# Domino_Pi.net
KiCad netlist of a schematic drawn in EAGLE
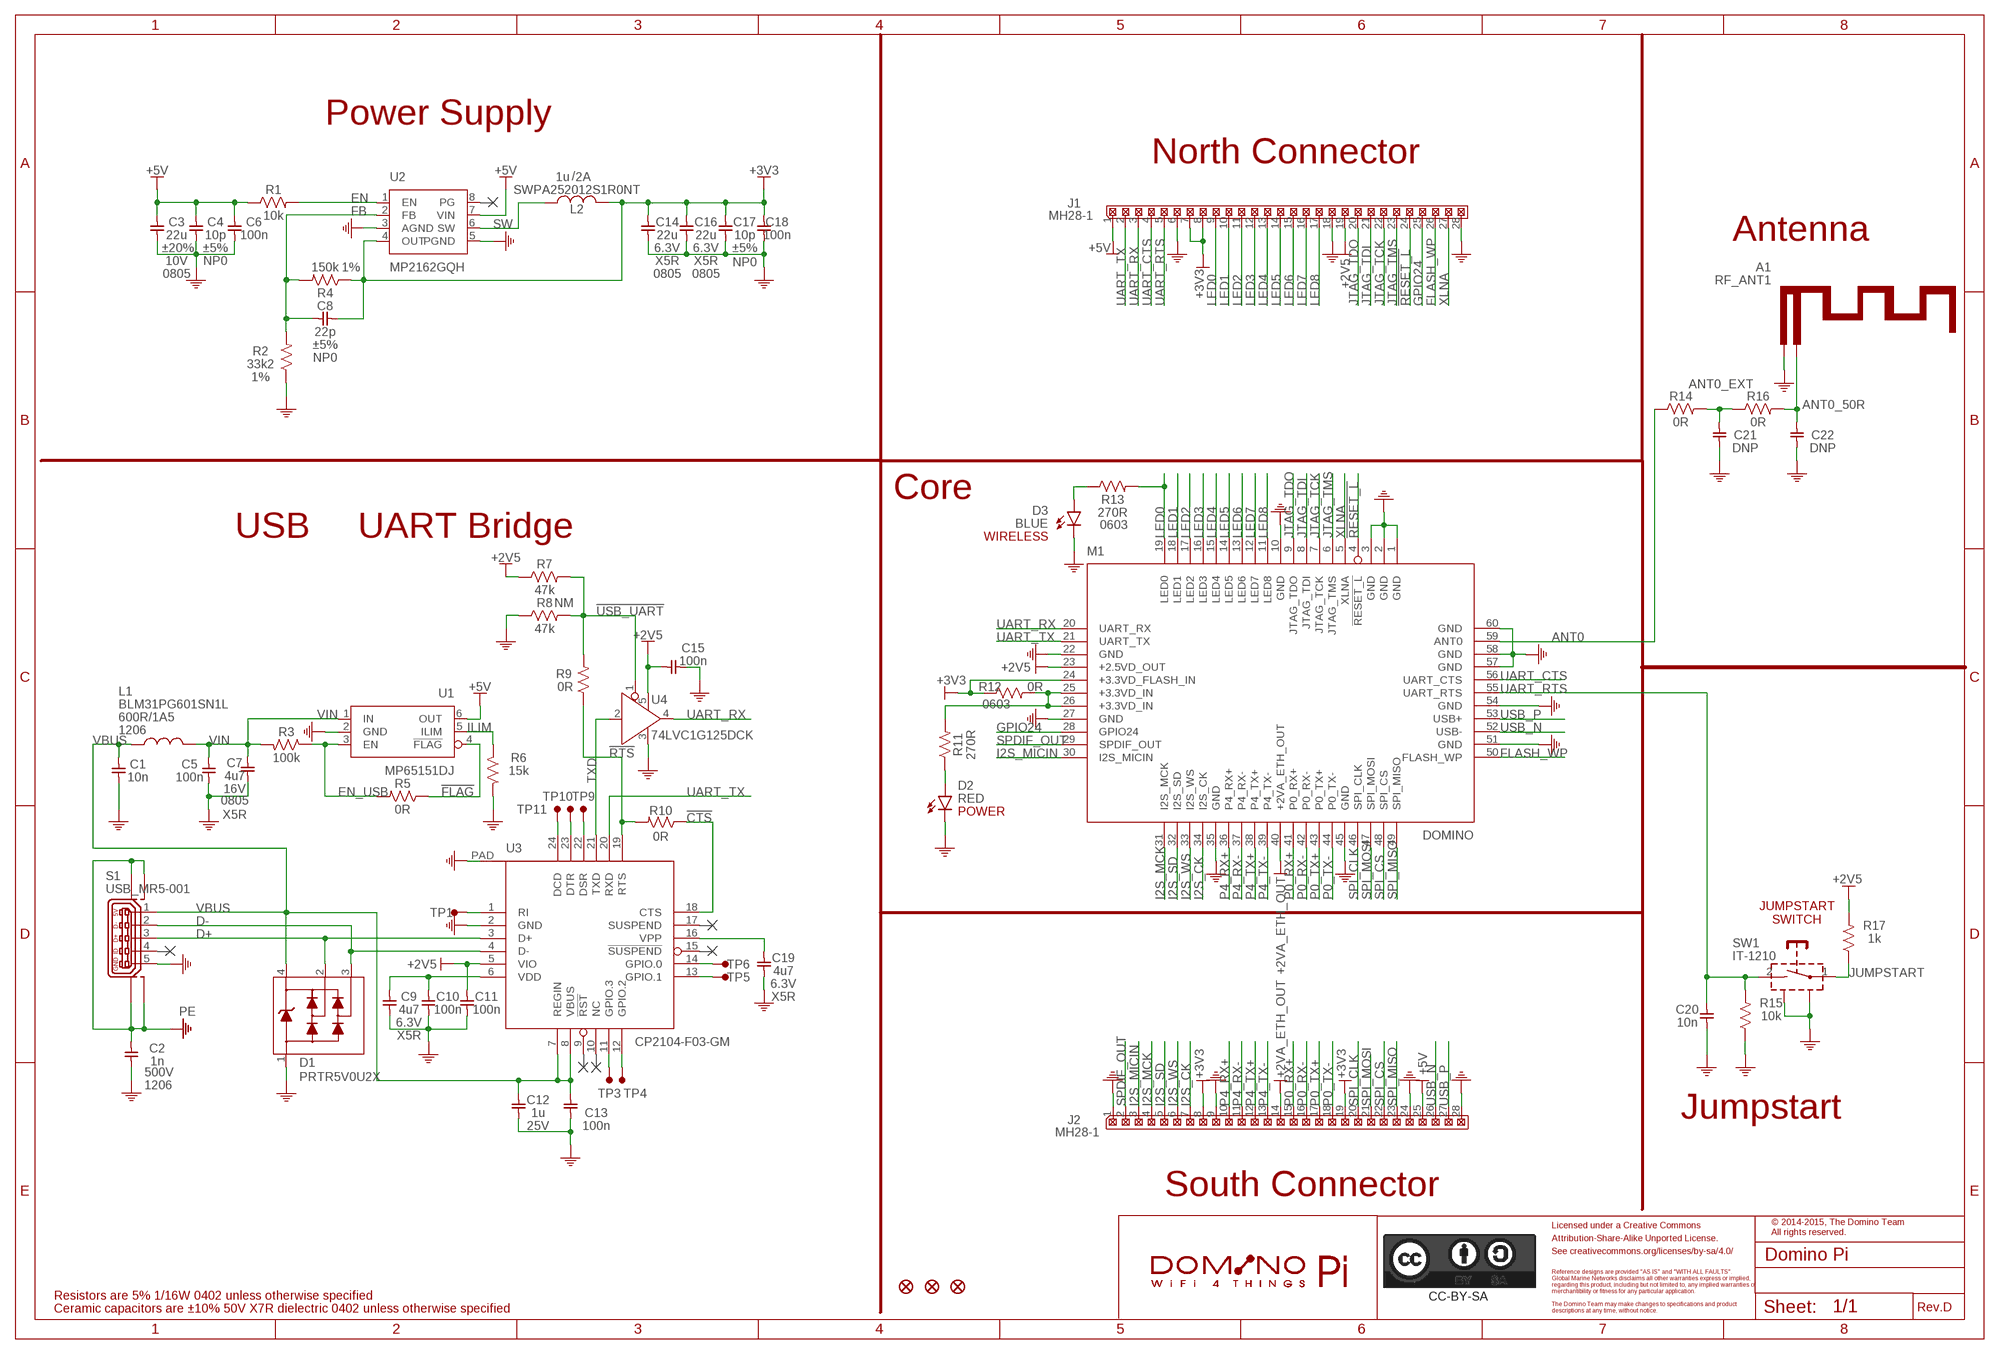
[diagram p0: schematic, sheet 1]

(export (version "E")
  (design (tool "Eeschema 10.0.6"))
  (components
    (comp (ref "A1")
      (value "RF_ANT1")
      (footprint "eagle-import:RF_ANT1")
      (fields (field (name "PARTNO") "WIFI_ANT-2.4GHz"))
      (libsource (lib "eagle-import") (part "RF_ANT1"))
    )
    (comp (ref "C1")
      (value "10n")
      (footprint "eagle-import:C0402")
      (fields (field (name "PARTNO") "C0402_10n_X7R_10%_CER_50V"))
      (libsource (lib "eagle-import") (part "CAP_0402"))
    )
    (comp (ref "C2")
      (value "1n")
      (footprint "eagle-import:C1206")
      (fields
        (field (name "SIZE") "1206")
        (field (name "PARTNO") "C1206_1n_X7R_10%_CER_500V")
        (field (name "VOLT") "500V")
      )
      (libsource (lib "eagle-import") (part "CAP_1206"))
    )
    (comp (ref "C3")
      (value "22u")
      (footprint "eagle-import:C0805")
      (fields
        (field (name "SIZE") "0805")
        (field (name "PARTNO") "C1206_22u_X7R_20%_CER_10V")
        (field (name "TOL") "±20%")
        (field (name "VOLT") "10V")
      )
      (libsource (lib "eagle-import") (part "CAP_0805"))
    )
    (comp (ref "C4")
      (value "10p")
      (footprint "eagle-import:C0402")
      (fields
        (field (name "PARTNO") "C0402_10p_NP0_5%_CER_50V")
        (field (name "TC") "NP0")
        (field (name "TOL") "±5%")
      )
      (libsource (lib "eagle-import") (part "CAP_0402"))
    )
    (comp (ref "C5")
      (value "100n")
      (footprint "eagle-import:C0402")
      (fields (field (name "PARTNO") "C0402_100n_X7R_10%_CER_50V"))
      (libsource (lib "eagle-import") (part "CAP_0402"))
    )
    (comp (ref "C6")
      (value "100n")
      (footprint "eagle-import:C0402")
      (fields (field (name "PARTNO") "C0402_100n_X7R_10%_CER_50V"))
      (libsource (lib "eagle-import") (part "CAP_0402"))
    )
    (comp (ref "C7")
      (value "4u7")
      (footprint "eagle-import:C0805")
      (fields
        (field (name "SIZE") "0805")
        (field (name "PARTNO") "C0805_4u7_X5R_10%_CER_16V")
        (field (name "TC") "X5R")
        (field (name "VOLT") "16V")
      )
      (libsource (lib "eagle-import") (part "CAP_0805"))
    )
    (comp (ref "C8")
      (value "22p")
      (footprint "eagle-import:C0402")
      (fields
        (field (name "PARTNO") "C0402_22p_NP0_5%_CER_50V")
        (field (name "TC") "NP0")
        (field (name "TOL") "±5%")
      )
      (libsource (lib "eagle-import") (part "CAP_0402"))
    )
    (comp (ref "C9")
      (value "4u7")
      (footprint "eagle-import:C0402")
      (fields
        (field (name "PARTNO") "C0402_4u7_X5R_10%_CER_6V3")
        (field (name "TC") "X5R")
        (field (name "VOLT") "6.3V")
      )
      (libsource (lib "eagle-import") (part "CAP_0402"))
    )
    (comp (ref "C10")
      (value "100n")
      (footprint "eagle-import:C0402")
      (fields (field (name "PARTNO") "C0402_100n_X7R_10%_CER_50V"))
      (libsource (lib "eagle-import") (part "CAP_0402"))
    )
    (comp (ref "C11")
      (value "100n")
      (footprint "eagle-import:C0402")
      (fields (field (name "PARTNO") "C0402_100n_X7R_10%_CER_50V"))
      (libsource (lib "eagle-import") (part "CAP_0402"))
    )
    (comp (ref "C12")
      (value "1u")
      (footprint "eagle-import:C0402")
      (fields (field (name "PARTNO") "C0402_1u_X7R_10%_CER_25V") (field (name "VOLT") "25V"))
      (libsource (lib "eagle-import") (part "CAP_0402"))
    )
    (comp (ref "C13")
      (value "100n")
      (footprint "eagle-import:C0402")
      (fields (field (name "PARTNO") "C0402_100n_X7R_10%_CER_50V"))
      (libsource (lib "eagle-import") (part "CAP_0402"))
    )
    (comp (ref "C14")
      (value "22u")
      (footprint "eagle-import:C0805")
      (fields
        (field (name "SIZE") "0805")
        (field (name "PARTNO") "C0805_22u_X5R_20%_CER_6V3")
        (field (name "TC") "X5R")
        (field (name "VOLT") "6.3V")
      )
      (libsource (lib "eagle-import") (part "CAP_0805"))
    )
    (comp (ref "C15")
      (value "100n")
      (footprint "eagle-import:C0402")
      (fields (field (name "PARTNO") "C0402_100n_X7R_10%_CER_50V"))
      (libsource (lib "eagle-import") (part "CAP_0402"))
    )
    (comp (ref "C16")
      (value "22u")
      (footprint "eagle-import:C0805")
      (fields
        (field (name "SIZE") "0805")
        (field (name "PARTNO") "C0805_22u_X5R_20%_CER_6V3")
        (field (name "TC") "X5R")
        (field (name "VOLT") "6.3V")
      )
      (libsource (lib "eagle-import") (part "CAP_0805"))
    )
    (comp (ref "C17")
      (value "10p")
      (footprint "eagle-import:C0402")
      (fields
        (field (name "PARTNO") "C0402_10p_NP0_5%_CER_50V")
        (field (name "TC") "NP0")
        (field (name "TOL") "±5%")
      )
      (libsource (lib "eagle-import") (part "CAP_0402"))
    )
    (comp (ref "C18")
      (value "100n")
      (footprint "eagle-import:C0402")
      (fields (field (name "PARTNO") "C0402_100n_X7R_10%_CER_50V"))
      (libsource (lib "eagle-import") (part "CAP_0402"))
    )
    (comp (ref "C19")
      (value "4u7")
      (footprint "eagle-import:C0402")
      (fields
        (field (name "PARTNO") "C0402_4u7_X5R_10%_CER_6V3")
        (field (name "TC") "X5R")
        (field (name "VOLT") "6.3V")
      )
      (libsource (lib "eagle-import") (part "CAP_0402"))
    )
    (comp (ref "C20")
      (value "10n")
      (footprint "eagle-import:C0402")
      (fields (field (name "PARTNO") "C0402_10n_X7R_10%_CER_50V"))
      (libsource (lib "eagle-import") (part "CAP_0402"))
    )
    (comp (ref "C21")
      (value "DNP")
      (footprint "eagle-import:C0402")
      (fields (field (name "PARTNO") "C0402_DNP"))
      (libsource (lib "eagle-import") (part "CAP_0402"))
    )
    (comp (ref "C22")
      (value "DNP")
      (footprint "eagle-import:C0402")
      (fields (field (name "PARTNO") "C0402_DNP"))
      (libsource (lib "eagle-import") (part "CAP_0402"))
    )
    (comp (ref "CC-BY-SA")
      (value "CC-BY-SA_LOGO")
      (footprint "eagle-import:CC-BY-SA_LOGO")
      (libsource (lib "eagle-import") (part "CC-BY-SA_LOGO"))
    )
    (comp (ref "D1")
      (value "PRTR5V0U2X")
      (footprint "eagle-import:SOT143B")
      (libsource (lib "eagle-import") (part "PRTR5V0U2X"))
    )
    (comp (ref "D2")
      (value "RED")
      (footprint "eagle-import:LED0402")
      (fields (field (name "PARTNO") "LED0402-RED"))
      (libsource (lib "eagle-import") (part "LED_0402"))
    )
    (comp (ref "D3")
      (value "BLUE")
      (footprint "eagle-import:LED0402")
      (fields (field (name "PARTNO") "LED0402-BLUE"))
      (libsource (lib "eagle-import") (part "LED_0402"))
    )
    (comp (ref "F1")
      (value "FIDUCIAL")
      (footprint "eagle-import:FIDUCIAL")
      (libsource (lib "eagle-import") (part "FIDUCIAL"))
    )
    (comp (ref "F2")
      (value "FIDUCIAL")
      (footprint "eagle-import:FIDUCIAL")
      (libsource (lib "eagle-import") (part "FIDUCIAL"))
    )
    (comp (ref "F3")
      (value "FIDUCIAL")
      (footprint "eagle-import:FIDUCIAL")
      (libsource (lib "eagle-import") (part "FIDUCIAL"))
    )
    (comp (ref "J1")
      (value "MH28-1")
      (footprint "eagle-import:MH28-1-0.1")
      (fields (field (name "PARTNO") "MH28-1-0.1"))
      (libsource (lib "eagle-import") (part "MH28-1"))
    )
    (comp (ref "J2")
      (value "MH28-1")
      (footprint "eagle-import:MH28-1-0.1")
      (fields (field (name "PARTNO") "MH28-1-0.1"))
      (libsource (lib "eagle-import") (part "MH28-1"))
    )
    (comp (ref "L1")
      (value "BLM31PG601SN1L")
      (footprint "eagle-import:FB1206")
      (fields (field (name "SIZE") "1206") (field (name "OPT") "600R/1A5"))
      (libsource (lib "eagle-import") (part "FB_1206"))
    )
    (comp (ref "L2")
      (value "SWPA252012S1R0NT")
      (footprint "eagle-import:SWPA252012S")
      (fields
        (field (name "INDUCTANCE") "1u")
        (field (name "RATE") "2A")
        (field (name "PARTNO") "SWPA252012SMT")
        (field (name "RATE_1") "2A")
      )
      (libsource (lib "eagle-import") (part "SWPA252012S?NT1R0"))
    )
    (comp (ref "M1")
      (value "DOMINO")
      (footprint "eagle-import:DOMINO")
      (fields (field (name "PARTNO") "DOMINO-CORE"))
      (libsource (lib "eagle-import") (part "DOMINO"))
    )
    (comp (ref "R1")
      (value "10k")
      (footprint "eagle-import:R0402")
      (fields (field (name "PARTNO") "R0402_10k_5%_62.5mW"))
      (libsource (lib "eagle-import") (part "RES_0402"))
    )
    (comp (ref "R2")
      (value "33k2")
      (footprint "eagle-import:R0402")
      (fields (field (name "PARTNO") "R0402_33k2_1%_62.5mW") (field (name "TOL") "1%"))
      (libsource (lib "eagle-import") (part "RES_0402"))
    )
    (comp (ref "R3")
      (value "100k")
      (footprint "eagle-import:R0402")
      (fields (field (name "PARTNO") "R0402_100k_5%_62.5mW"))
      (libsource (lib "eagle-import") (part "RES_0402"))
    )
    (comp (ref "R4")
      (value "150k")
      (footprint "eagle-import:R0402")
      (fields (field (name "PARTNO") "R0402_150k_1%_62.5mW") (field (name "TOL") "1%"))
      (libsource (lib "eagle-import") (part "RES_0402"))
    )
    (comp (ref "R5")
      (value "0R")
      (footprint "eagle-import:R0402")
      (fields (field (name "PARTNO") "R0402_0R_5%_62.5mW"))
      (libsource (lib "eagle-import") (part "RES_0402"))
    )
    (comp (ref "R6")
      (value "15k")
      (footprint "eagle-import:R0402")
      (fields (field (name "PARTNO") "R0402_15k_5%_62.5mW"))
      (libsource (lib "eagle-import") (part "RES_0402"))
    )
    (comp (ref "R7")
      (value "47k")
      (footprint "eagle-import:R0402")
      (fields (field (name "PARTNO") "R0402_47k_5%_62.5mW"))
      (libsource (lib "eagle-import") (part "RES_0402"))
    )
    (comp (ref "R8")
      (value "47k")
      (footprint "eagle-import:R0402")
      (fields (field (name "PARTNO") "R0402_47k_5%_62.5mW"))
      (libsource (lib "eagle-import") (part "RES_0402"))
    )
    (comp (ref "R9")
      (value "0R")
      (footprint "eagle-import:R0402")
      (fields (field (name "PARTNO") "R0402_0R_5%_62.5mW"))
      (libsource (lib "eagle-import") (part "RES_0402"))
    )
    (comp (ref "R10")
      (value "0R")
      (footprint "eagle-import:R0402")
      (fields (field (name "PARTNO") "R0402_0R_5%_62.5mW"))
      (libsource (lib "eagle-import") (part "RES_0402"))
    )
    (comp (ref "R11")
      (value "270R")
      (footprint "eagle-import:R0402")
      (fields (field (name "PARTNO") "R0402_270R_5%_62.5mW"))
      (libsource (lib "eagle-import") (part "RES_0402"))
    )
    (comp (ref "R12")
      (value "0R")
      (footprint "eagle-import:R0603")
      (fields (field (name "SIZE") "0603") (field (name "PARTNO") "R0603_0R_5%_125mW"))
      (libsource (lib "eagle-import") (part "RES_0603"))
    )
    (comp (ref "R13")
      (value "270R")
      (footprint "eagle-import:R0603")
      (fields (field (name "SIZE") "0603") (field (name "PARTNO") "R0603_270R_5%_125mW"))
      (libsource (lib "eagle-import") (part "RES_0603"))
    )
    (comp (ref "R14")
      (value "0R")
      (footprint "eagle-import:R0402")
      (fields (field (name "PARTNO") "R0402_0R_5%_62.5mW"))
      (libsource (lib "eagle-import") (part "RES_0402"))
    )
    (comp (ref "R15")
      (value "10k")
      (footprint "eagle-import:R0402")
      (fields (field (name "PARTNO") "R0402_10k_5%_62.5mW"))
      (libsource (lib "eagle-import") (part "RES_0402"))
    )
    (comp (ref "R16")
      (value "0R")
      (footprint "eagle-import:R0402")
      (fields (field (name "PARTNO") "R0402_0R_5%_62.5mW"))
      (libsource (lib "eagle-import") (part "RES_0402"))
    )
    (comp (ref "R17")
      (value "1k")
      (footprint "eagle-import:R0402")
      (fields (field (name "PARTNO") "R0402_1k_5%_62.5mW"))
      (libsource (lib "eagle-import") (part "RES_0402"))
    )
    (comp (ref "S1")
      (value "USB_MR5-001")
      (footprint "eagle-import:USB-MR5-001")
      (fields (field (name "PARTNO") "USB MR5-001"))
      (libsource (lib "eagle-import") (part "USB_MR5-001"))
    )
    (comp (ref "SW1")
      (value "IT-1210")
      (footprint "eagle-import:IT-1210")
      (libsource (lib "eagle-import") (part "IT-1210"))
    )
    (comp (ref "TP1")
      (value "TEST_PAD")
      (footprint "eagle-import:TEST_PAD")
      (libsource (lib "eagle-import") (part "TEST_PAD"))
    )
    (comp (ref "TP3")
      (value "TEST_PAD")
      (footprint "eagle-import:TEST_PAD")
      (libsource (lib "eagle-import") (part "TEST_PAD"))
    )
    (comp (ref "TP4")
      (value "TEST_PAD")
      (footprint "eagle-import:TEST_PAD")
      (libsource (lib "eagle-import") (part "TEST_PAD"))
    )
    (comp (ref "TP5")
      (value "TEST_PAD")
      (footprint "eagle-import:TEST_PAD")
      (libsource (lib "eagle-import") (part "TEST_PAD"))
    )
    (comp (ref "TP6")
      (value "TEST_PAD")
      (footprint "eagle-import:TEST_PAD")
      (libsource (lib "eagle-import") (part "TEST_PAD"))
    )
    (comp (ref "TP9")
      (value "TEST_PAD")
      (footprint "eagle-import:TEST_PAD")
      (libsource (lib "eagle-import") (part "TEST_PAD"))
    )
    (comp (ref "TP10")
      (value "TEST_PAD")
      (footprint "eagle-import:TEST_PAD")
      (libsource (lib "eagle-import") (part "TEST_PAD"))
    )
    (comp (ref "TP11")
      (value "TEST_PAD")
      (footprint "eagle-import:TEST_PAD")
      (libsource (lib "eagle-import") (part "TEST_PAD"))
    )
    (comp (ref "U1")
      (value "MP65151DJ")
      (footprint "eagle-import:SOT23-6")
      (libsource (lib "eagle-import") (part "MP65151DJ"))
    )
    (comp (ref "U2")
      (value "MP2162GQH")
      (footprint "eagle-import:QFN-8_2X1.5")
      (libsource (lib "eagle-import") (part "MP2162GQH"))
    )
    (comp (ref "U3")
      (value "CP2104-F03-GM")
      (footprint "eagle-import:QFN-25_4X4")
      (libsource (lib "eagle-import") (part "CP2104-F03-GM"))
    )
    (comp (ref "U4")
      (value "74LVC1G125DCK")
      (footprint "eagle-import:SC70")
      (fields (field (name "PARTNO") "74LVC1G125DCK "))
      (libsource (lib "eagle-import") (part "741G125DCKLVC"))
    )
    (comp (ref "W1")
      (value "DOMINO_PI_LOGO")
      (footprint "eagle-import:DOMINO_PI_LOGO")
      (libsource (lib "eagle-import") (part "DOMINO_PI_LOGO"))
    )
  )
  (nets
    (net (code "1") (name "+2V5") (class "Default")
      (node (ref "C11") (pin "1") (pinfunction "1_1") (pintype "passive"))
      (node (ref "C15") (pin "2") (pinfunction "2_2") (pintype "passive"))
      (node (ref "J1") (pin "19") (pinfunction "19_19") (pintype "passive"))
      (node (ref "M1") (pin "23") (pinfunction "+2.5VD_OUT_23") (pintype "power_in"))
      (node (ref "R17") (pin "2") (pinfunction "2_2") (pintype "passive"))
      (node (ref "R7") (pin "1") (pinfunction "1_1") (pintype "passive"))
      (node (ref "U3") (pin "5") (pinfunction "VIO_5") (pintype "power_in"))
      (node (ref "U4") (pin "5") (pinfunction "VCC_5") (pintype "power_in"))
    )
    (net (code "2") (name "+2VA_ETH_OUT") (class "Default")
      (node (ref "J2") (pin "14") (pinfunction "14_14") (pintype "passive"))
      (node (ref "M1") (pin "40") (pinfunction "+2VA_ETH_OUT_40") (pintype "power_in"))
    )
    (net (code "3") (name "+3V3") (class "Default")
      (node (ref "C14") (pin "1") (pinfunction "1_1") (pintype "passive"))
      (node (ref "C16") (pin "1") (pinfunction "1_1") (pintype "passive"))
      (node (ref "C17") (pin "1") (pinfunction "1_1") (pintype "passive"))
      (node (ref "C18") (pin "1") (pinfunction "1_1") (pintype "passive"))
      (node (ref "C8") (pin "2") (pinfunction "2_2") (pintype "passive"))
      (node (ref "J1") (pin "7") (pinfunction "7_7") (pintype "passive"))
      (node (ref "J1") (pin "8") (pinfunction "8_8") (pintype "passive"))
      (node (ref "J2") (pin "19") (pinfunction "19_19") (pintype "passive"))
      (node (ref "J2") (pin "8") (pinfunction "8_8") (pintype "passive"))
      (node (ref "L2") (pin "2") (pinfunction "2_2") (pintype "passive"))
      (node (ref "M1") (pin "24") (pinfunction "+3.3VD_FLASH_IN_24") (pintype "power_in"))
      (node (ref "R12") (pin "1") (pinfunction "1_1") (pintype "passive"))
      (node (ref "R4") (pin "1") (pinfunction "1_1") (pintype "passive"))
      (node (ref "U2") (pin "4") (pinfunction "OUT_4") (pintype "power_in"))
    )
    (net (code "4") (name "+5V") (class "Default")
      (node (ref "C3") (pin "1") (pinfunction "1_1") (pintype "passive"))
      (node (ref "C4") (pin "1") (pinfunction "1_1") (pintype "passive"))
      (node (ref "C6") (pin "1") (pinfunction "1_1") (pintype "passive"))
      (node (ref "J1") (pin "1") (pinfunction "1_1") (pintype "passive"))
      (node (ref "J2") (pin "25") (pinfunction "25_25") (pintype "passive"))
      (node (ref "R1") (pin "1") (pinfunction "1_1") (pintype "passive"))
      (node (ref "U1") (pin "6") (pinfunction "OUT_6") (pintype "power_in"))
      (node (ref "U2") (pin "7") (pinfunction "VIN_7") (pintype "power_in"))
    )
    (net (code "5") (name "/ANT0") (class "Default")
      (node (ref "M1") (pin "59") (pinfunction "ANT0_59") (pintype "passive"))
      (node (ref "R14") (pin "1") (pinfunction "1_1") (pintype "passive"))
    )
    (net (code "6") (name "/ANT0_50R") (class "Default")
      (node (ref "A1") (pin "FEED") (pinfunction "FEED_FEED") (pintype "passive"))
      (node (ref "C22") (pin "1") (pinfunction "1_1") (pintype "passive"))
      (node (ref "R16") (pin "2") (pinfunction "2_2") (pintype "passive"))
    )
    (net (code "7") (name "/ANT0_EXT") (class "Default")
      (node (ref "C21") (pin "1") (pinfunction "1_1") (pintype "passive"))
      (node (ref "R14") (pin "2") (pinfunction "2_2") (pintype "passive"))
      (node (ref "R16") (pin "1") (pinfunction "1_1") (pintype "passive"))
    )
    (net (code "8") (name "/D+") (class "Default")
      (node (ref "D1") (pin "2") (pinfunction "P$2_2") (pintype "passive"))
      (node (ref "S1") (pin "3") (pinfunction "3_3") (pintype "passive"))
      (node (ref "U3") (pin "3") (pinfunction "D+_3") (pintype "passive"))
    )
    (net (code "9") (name "/D-") (class "Default")
      (node (ref "D1") (pin "3") (pinfunction "P$3_3") (pintype "passive"))
      (node (ref "S1") (pin "2") (pinfunction "2_2") (pintype "passive"))
      (node (ref "U3") (pin "4") (pinfunction "D-_4") (pintype "passive"))
    )
    (net (code "10") (name "/EN") (class "Default")
      (node (ref "R1") (pin "2") (pinfunction "2_2") (pintype "passive"))
      (node (ref "U2") (pin "1") (pinfunction "EN_1") (pintype "input"))
    )
    (net (code "11") (name "/EN_USB") (class "Default")
      (node (ref "R3") (pin "1") (pinfunction "1_1") (pintype "passive"))
      (node (ref "R5") (pin "2") (pinfunction "2_2") (pintype "passive"))
      (node (ref "U1") (pin "3") (pinfunction "EN_3") (pintype "input"))
    )
    (net (code "12") (name "/FB") (class "Default")
      (node (ref "C8") (pin "1") (pinfunction "1_1") (pintype "passive"))
      (node (ref "R2") (pin "2") (pinfunction "2_2") (pintype "passive"))
      (node (ref "R4") (pin "2") (pinfunction "2_2") (pintype "passive"))
      (node (ref "U2") (pin "2") (pinfunction "FB_2") (pintype "passive"))
    )
    (net (code "13") (name "/FLASH_WP") (class "Default")
      (node (ref "J1") (pin "26") (pinfunction "26_26") (pintype "passive"))
      (node (ref "M1") (pin "50") (pinfunction "FLASH_WP_50") (pintype "bidirectional"))
    )
    (net (code "14") (name "/GPIO24") (class "Default")
      (node (ref "J1") (pin "25") (pinfunction "25_25") (pintype "passive"))
      (node (ref "M1") (pin "28") (pinfunction "GPIO24_28") (pintype "bidirectional"))
    )
    (net (code "15") (name "/I2S_CK") (class "Default")
      (node (ref "J2") (pin "7") (pinfunction "7_7") (pintype "passive"))
      (node (ref "M1") (pin "34") (pinfunction "I2S_CK_34") (pintype "bidirectional"))
    )
    (net (code "16") (name "/I2S_MCK") (class "Default")
      (node (ref "J2") (pin "4") (pinfunction "4_4") (pintype "passive"))
      (node (ref "M1") (pin "31") (pinfunction "I2S_MCK_31") (pintype "bidirectional"))
    )
    (net (code "17") (name "/I2S_MICIN") (class "Default")
      (node (ref "J2") (pin "3") (pinfunction "3_3") (pintype "passive"))
      (node (ref "M1") (pin "30") (pinfunction "I2S_MICIN_30") (pintype "bidirectional"))
    )
    (net (code "18") (name "/I2S_SD") (class "Default")
      (node (ref "J2") (pin "5") (pinfunction "5_5") (pintype "passive"))
      (node (ref "M1") (pin "32") (pinfunction "I2S_SD_32") (pintype "bidirectional"))
    )
    (net (code "19") (name "/I2S_WS") (class "Default")
      (node (ref "J2") (pin "6") (pinfunction "6_6") (pintype "passive"))
      (node (ref "M1") (pin "33") (pinfunction "I2S_WS_33") (pintype "bidirectional"))
    )
    (net (code "20") (name "/ILIM") (class "Default")
      (node (ref "R6") (pin "1") (pinfunction "1_1") (pintype "passive"))
      (node (ref "U1") (pin "5") (pinfunction "ILIM_5") (pintype "passive"))
    )
    (net (code "21") (name "/JTAG_TCK") (class "Default")
      (node (ref "J1") (pin "22") (pinfunction "22_22") (pintype "passive"))
      (node (ref "M1") (pin "7") (pinfunction "JTAG_TCK_7") (pintype "bidirectional"))
    )
    (net (code "22") (name "/JTAG_TDI") (class "Default")
      (node (ref "J1") (pin "21") (pinfunction "21_21") (pintype "passive"))
      (node (ref "M1") (pin "8") (pinfunction "JTAG_TDI_8") (pintype "bidirectional"))
    )
    (net (code "23") (name "/JTAG_TDO") (class "Default")
      (node (ref "J1") (pin "20") (pinfunction "20_20") (pintype "passive"))
      (node (ref "M1") (pin "9") (pinfunction "JTAG_TDO_9") (pintype "bidirectional"))
    )
    (net (code "24") (name "/JTAG_TMS") (class "Default")
      (node (ref "J1") (pin "23") (pinfunction "23_23") (pintype "passive"))
      (node (ref "M1") (pin "6") (pinfunction "JTAG_TMS_6") (pintype "bidirectional"))
    )
    (net (code "25") (name "/JUMPSTART") (class "Default")
      (node (ref "R17") (pin "1") (pinfunction "1_1") (pintype "passive"))
      (node (ref "SW1") (pin "1") (pinfunction "1_1") (pintype "passive"))
    )
    (net (code "26") (name "/LED0") (class "Default")
      (node (ref "J1") (pin "9") (pinfunction "9_9") (pintype "passive"))
      (node (ref "M1") (pin "19") (pinfunction "LED0_19") (pintype "bidirectional"))
      (node (ref "R13") (pin "2") (pinfunction "2_2") (pintype "passive"))
    )
    (net (code "27") (name "/LED1") (class "Default")
      (node (ref "J1") (pin "10") (pinfunction "10_10") (pintype "passive"))
      (node (ref "M1") (pin "18") (pinfunction "LED1_18") (pintype "bidirectional"))
    )
    (net (code "28") (name "/LED2") (class "Default")
      (node (ref "J1") (pin "11") (pinfunction "11_11") (pintype "passive"))
      (node (ref "M1") (pin "17") (pinfunction "LED2_17") (pintype "bidirectional"))
    )
    (net (code "29") (name "/LED3") (class "Default")
      (node (ref "J1") (pin "12") (pinfunction "12_12") (pintype "passive"))
      (node (ref "M1") (pin "16") (pinfunction "LED3_16") (pintype "bidirectional"))
    )
    (net (code "30") (name "/LED4") (class "Default")
      (node (ref "J1") (pin "13") (pinfunction "13_13") (pintype "passive"))
      (node (ref "M1") (pin "15") (pinfunction "LED4_15") (pintype "bidirectional"))
    )
    (net (code "31") (name "/LED5") (class "Default")
      (node (ref "J1") (pin "14") (pinfunction "14_14") (pintype "passive"))
      (node (ref "M1") (pin "14") (pinfunction "LED5_14") (pintype "bidirectional"))
    )
    (net (code "32") (name "/LED6") (class "Default")
      (node (ref "J1") (pin "15") (pinfunction "15_15") (pintype "passive"))
      (node (ref "M1") (pin "13") (pinfunction "LED6_13") (pintype "bidirectional"))
    )
    (net (code "33") (name "/LED7") (class "Default")
      (node (ref "J1") (pin "16") (pinfunction "16_16") (pintype "passive"))
      (node (ref "M1") (pin "12") (pinfunction "LED7_12") (pintype "bidirectional"))
    )
    (net (code "34") (name "/LED8") (class "Default")
      (node (ref "J1") (pin "17") (pinfunction "17_17") (pintype "passive"))
      (node (ref "M1") (pin "11") (pinfunction "LED8_11") (pintype "bidirectional"))
    )
    (net (code "35") (name "/P0_RX+") (class "Default")
      (node (ref "J2") (pin "15") (pinfunction "15_15") (pintype "passive"))
      (node (ref "M1") (pin "41") (pinfunction "P0_RX+_41") (pintype "passive"))
    )
    (net (code "36") (name "/P0_RX-") (class "Default")
      (node (ref "J2") (pin "16") (pinfunction "16_16") (pintype "passive"))
      (node (ref "M1") (pin "42") (pinfunction "P0_RX-_42") (pintype "passive"))
    )
    (net (code "37") (name "/P0_TX+") (class "Default")
      (node (ref "J2") (pin "17") (pinfunction "17_17") (pintype "passive"))
      (node (ref "M1") (pin "43") (pinfunction "P0_TX+_43") (pintype "passive"))
    )
    (net (code "38") (name "/P0_TX-") (class "Default")
      (node (ref "J2") (pin "18") (pinfunction "18_18") (pintype "passive"))
      (node (ref "M1") (pin "44") (pinfunction "P0_TX-_44") (pintype "passive"))
    )
    (net (code "39") (name "/P4_RX+") (class "Default")
      (node (ref "J2") (pin "10") (pinfunction "10_10") (pintype "passive"))
      (node (ref "M1") (pin "36") (pinfunction "P4_RX+_36") (pintype "passive"))
    )
    (net (code "40") (name "/P4_RX-") (class "Default")
      (node (ref "J2") (pin "11") (pinfunction "11_11") (pintype "passive"))
      (node (ref "M1") (pin "37") (pinfunction "P4_RX-_37") (pintype "passive"))
    )
    (net (code "41") (name "/P4_TX+") (class "Default")
      (node (ref "J2") (pin "12") (pinfunction "12_12") (pintype "passive"))
      (node (ref "M1") (pin "38") (pinfunction "P4_TX+_38") (pintype "passive"))
    )
    (net (code "42") (name "/P4_TX-") (class "Default")
      (node (ref "J2") (pin "13") (pinfunction "13_13") (pintype "passive"))
      (node (ref "M1") (pin "39") (pinfunction "P4_TX-_39") (pintype "passive"))
    )
    (net (code "43") (name "/SPDIF_OUT") (class "Default")
      (node (ref "J2") (pin "2") (pinfunction "2_2") (pintype "passive"))
      (node (ref "M1") (pin "29") (pinfunction "SPDIF_OUT_29") (pintype "bidirectional"))
    )
    (net (code "44") (name "/SPI_CLK") (class "Default")
      (node (ref "J2") (pin "20") (pinfunction "20_20") (pintype "passive"))
      (node (ref "M1") (pin "46") (pinfunction "SPI_CLK_46") (pintype "bidirectional"))
    )
    (net (code "45") (name "/SPI_CS") (class "Default")
      (node (ref "J2") (pin "22") (pinfunction "22_22") (pintype "passive"))
      (node (ref "M1") (pin "48") (pinfunction "SPI_CS_48") (pintype "bidirectional"))
    )
    (net (code "46") (name "/SPI_MISO") (class "Default")
      (node (ref "J2") (pin "23") (pinfunction "23_23") (pintype "passive"))
      (node (ref "M1") (pin "49") (pinfunction "SPI_MISO_49") (pintype "bidirectional"))
    )
    (net (code "47") (name "/SPI_MOSI") (class "Default")
      (node (ref "J2") (pin "21") (pinfunction "21_21") (pintype "passive"))
      (node (ref "M1") (pin "47") (pinfunction "SPI_MOSI_47") (pintype "bidirectional"))
    )
    (net (code "48") (name "/SW") (class "Default")
      (node (ref "L2") (pin "1") (pinfunction "1_1") (pintype "passive"))
      (node (ref "U2") (pin "6") (pinfunction "SW_6") (pintype "passive"))
    )
    (net (code "49") (name "/TXD") (class "Default")
      (node (ref "U3") (pin "21") (pinfunction "TXD_21") (pintype "output"))
      (node (ref "U4") (pin "2") (pinfunction "A_2") (pintype "input"))
    )
    (net (code "50") (name "/UART_CTS") (class "Default")
      (node (ref "J1") (pin "4") (pinfunction "4_4") (pintype "passive"))
      (node (ref "M1") (pin "56") (pinfunction "UART_CTS_56") (pintype "bidirectional"))
    )
    (net (code "51") (name "/UART_RTS") (class "Default")
      (node (ref "C20") (pin "1") (pinfunction "1_1") (pintype "passive"))
      (node (ref "J1") (pin "5") (pinfunction "5_5") (pintype "passive"))
      (node (ref "M1") (pin "55") (pinfunction "UART_RTS_55") (pintype "bidirectional"))
      (node (ref "R15") (pin "2") (pinfunction "2_2") (pintype "passive"))
      (node (ref "SW1") (pin "2") (pinfunction "2_2") (pintype "passive"))
    )
    (net (code "52") (name "/UART_RX") (class "Default")
      (node (ref "J1") (pin "3") (pinfunction "3_3") (pintype "passive"))
      (node (ref "M1") (pin "20") (pinfunction "UART_RX_20") (pintype "bidirectional"))
      (node (ref "U4") (pin "4") (pinfunction "Y_4") (pintype "tri_state"))
    )
    (net (code "53") (name "/UART_TX") (class "Default")
      (node (ref "J1") (pin "2") (pinfunction "2_2") (pintype "passive"))
      (node (ref "M1") (pin "21") (pinfunction "UART_TX_21") (pintype "bidirectional"))
      (node (ref "U3") (pin "20") (pinfunction "RXD_20") (pintype "input"))
    )
    (net (code "54") (name "/USB_N") (class "Default")
      (node (ref "J2") (pin "26") (pinfunction "26_26") (pintype "passive"))
      (node (ref "M1") (pin "52") (pinfunction "USB-_52") (pintype "passive"))
    )
    (net (code "55") (name "/USB_P") (class "Default")
      (node (ref "J2") (pin "27") (pinfunction "27_27") (pintype "passive"))
      (node (ref "M1") (pin "53") (pinfunction "USB+_53") (pintype "passive"))
    )
    (net (code "56") (name "/VBUS") (class "Default")
      (node (ref "C1") (pin "1") (pinfunction "1_1") (pintype "passive"))
      (node (ref "C12") (pin "1") (pinfunction "1_1") (pintype "passive"))
      (node (ref "C13") (pin "1") (pinfunction "1_1") (pintype "passive"))
      (node (ref "D1") (pin "4") (pinfunction "P$4_4") (pintype "passive"))
      (node (ref "L1") (pin "2") (pinfunction "2_2") (pintype "passive"))
      (node (ref "S1") (pin "1") (pinfunction "1_1") (pintype "passive"))
      (node (ref "U3") (pin "7") (pinfunction "REGIN_7") (pintype "power_in"))
      (node (ref "U3") (pin "8") (pinfunction "VBUS_8") (pintype "input"))
    )
    (net (code "57") (name "/VIN") (class "Default")
      (node (ref "C5") (pin "1") (pinfunction "1_1") (pintype "passive"))
      (node (ref "C7") (pin "1") (pinfunction "1_1") (pintype "passive"))
      (node (ref "L1") (pin "1") (pinfunction "1_1") (pintype "passive"))
      (node (ref "R3") (pin "2") (pinfunction "2_2") (pintype "passive"))
      (node (ref "U1") (pin "1") (pinfunction "IN_1") (pintype "power_in"))
    )
    (net (code "58") (name "/XLNA") (class "Default")
      (node (ref "J1") (pin "27") (pinfunction "27_27") (pintype "passive"))
      (node (ref "M1") (pin "5") (pinfunction "XLNA_5") (pintype "bidirectional"))
    )
    (net (code "59") (name "/~{CTS}") (class "Default")
      (node (ref "R10") (pin "1") (pinfunction "1_1") (pintype "passive"))
      (node (ref "U3") (pin "18") (pinfunction "CTS_18") (pintype "input"))
    )
    (net (code "60") (name "/~{FLAG}") (class "Default")
      (node (ref "R5") (pin "1") (pinfunction "1_1") (pintype "passive"))
      (node (ref "U1") (pin "4") (pinfunction "~{FLAG}_4") (pintype "open_collector"))
    )
    (net (code "61") (name "/~{RESET_L}") (class "Default")
      (node (ref "J1") (pin "24") (pinfunction "24_24") (pintype "passive"))
      (node (ref "M1") (pin "4") (pinfunction "~{RESET_L}_4") (pintype "input"))
    )
    (net (code "62") (name "/~{RTS}") (class "Default")
      (node (ref "R10") (pin "2") (pinfunction "2_2") (pintype "passive"))
      (node (ref "R9") (pin "1") (pinfunction "1_1") (pintype "passive"))
      (node (ref "U3") (pin "19") (pinfunction "RTS_19") (pintype "output"))
    )
    (net (code "63") (name "/~{USB_UART}") (class "Default")
      (node (ref "R7") (pin "2") (pinfunction "2_2") (pintype "passive"))
      (node (ref "R8") (pin "2") (pinfunction "2_2") (pintype "passive"))
      (node (ref "R9") (pin "2") (pinfunction "2_2") (pintype "passive"))
      (node (ref "U4") (pin "1") (pinfunction "~{OE}_1") (pintype "input"))
    )
    (net (code "64") (name "GND") (class "Default")
      (node (ref "A1") (pin "GND") (pinfunction "GND_GND") (pintype "power_in"))
      (node (ref "C1") (pin "2") (pinfunction "2_2") (pintype "passive"))
      (node (ref "C10") (pin "2") (pinfunction "2_2") (pintype "passive"))
      (node (ref "C11") (pin "2") (pinfunction "2_2") (pintype "passive"))
      (node (ref "C12") (pin "2") (pinfunction "2_2") (pintype "passive"))
      (node (ref "C13") (pin "2") (pinfunction "2_2") (pintype "passive"))
      (node (ref "C14") (pin "2") (pinfunction "2_2") (pintype "passive"))
      (node (ref "C15") (pin "1") (pinfunction "1_1") (pintype "passive"))
      (node (ref "C16") (pin "2") (pinfunction "2_2") (pintype "passive"))
      (node (ref "C17") (pin "2") (pinfunction "2_2") (pintype "passive"))
      (node (ref "C18") (pin "2") (pinfunction "2_2") (pintype "passive"))
      (node (ref "C19") (pin "2") (pinfunction "2_2") (pintype "passive"))
      (node (ref "C2") (pin "2") (pinfunction "2_2") (pintype "passive"))
      (node (ref "C20") (pin "2") (pinfunction "2_2") (pintype "passive"))
      (node (ref "C21") (pin "2") (pinfunction "2_2") (pintype "passive"))
      (node (ref "C22") (pin "2") (pinfunction "2_2") (pintype "passive"))
      (node (ref "C3") (pin "2") (pinfunction "2_2") (pintype "passive"))
      (node (ref "C4") (pin "2") (pinfunction "2_2") (pintype "passive"))
      (node (ref "C5") (pin "2") (pinfunction "2_2") (pintype "passive"))
      (node (ref "C6") (pin "2") (pinfunction "2_2") (pintype "passive"))
      (node (ref "C7") (pin "2") (pinfunction "2_2") (pintype "passive"))
      (node (ref "C9") (pin "2") (pinfunction "2_2") (pintype "passive"))
      (node (ref "D1") (pin "1") (pinfunction "P$1_1") (pintype "passive"))
      (node (ref "D2") (pin "1") (pinfunction "C_1") (pintype "passive"))
      (node (ref "D3") (pin "1") (pinfunction "C_1") (pintype "passive"))
      (node (ref "J1") (pin "18") (pinfunction "18_18") (pintype "passive"))
      (node (ref "J1") (pin "28") (pinfunction "28_28") (pintype "passive"))
      (node (ref "J1") (pin "6") (pinfunction "6_6") (pintype "passive"))
      (node (ref "J2") (pin "1") (pinfunction "1_1") (pintype "passive"))
      (node (ref "J2") (pin "24") (pinfunction "24_24") (pintype "passive"))
      (node (ref "J2") (pin "28") (pinfunction "28_28") (pintype "passive"))
      (node (ref "J2") (pin "9") (pinfunction "9_9") (pintype "passive"))
      (node (ref "M1") (pin "1") (pinfunction "GND_1") (pintype "power_in"))
      (node (ref "M1") (pin "10") (pinfunction "GND_10") (pintype "power_in"))
      (node (ref "M1") (pin "2") (pinfunction "GND_2") (pintype "power_in"))
      (node (ref "M1") (pin "22") (pinfunction "GND_22") (pintype "power_in"))
      (node (ref "M1") (pin "27") (pinfunction "GND_27") (pintype "power_in"))
      (node (ref "M1") (pin "3") (pinfunction "GND_3") (pintype "power_in"))
      (node (ref "M1") (pin "35") (pinfunction "GND_35") (pintype "power_in"))
      (node (ref "M1") (pin "45") (pinfunction "GND_45") (pintype "power_in"))
      (node (ref "M1") (pin "51") (pinfunction "GND_51") (pintype "power_in"))
      (node (ref "M1") (pin "54") (pinfunction "GND_54") (pintype "power_in"))
      (node (ref "M1") (pin "57") (pinfunction "GND_57") (pintype "power_in"))
      (node (ref "M1") (pin "58") (pinfunction "GND_58") (pintype "power_in"))
      (node (ref "M1") (pin "60") (pinfunction "GND_60") (pintype "power_in"))
      (node (ref "R15") (pin "1") (pinfunction "1_1") (pintype "passive"))
      (node (ref "R2") (pin "1") (pinfunction "1_1") (pintype "passive"))
      (node (ref "R6") (pin "2") (pinfunction "2_2") (pintype "passive"))
      (node (ref "R8") (pin "1") (pinfunction "1_1") (pintype "passive"))
      (node (ref "S1") (pin "5") (pinfunction "5_5") (pintype "passive"))
      (node (ref "SW1") (pin "SH$1") (pinfunction "SH$1_SH$1") (pintype "passive"))
      (node (ref "SW1") (pin "SH$2") (pinfunction "SH$2_SH$2") (pintype "passive"))
      (node (ref "U1") (pin "2") (pinfunction "GND_2") (pintype "power_in"))
      (node (ref "U2") (pin "3") (pinfunction "AGND_3") (pintype "power_in"))
      (node (ref "U2") (pin "5") (pinfunction "PGND_5") (pintype "power_in"))
      (node (ref "U3") (pin "2") (pinfunction "GND_2") (pintype "power_in"))
      (node (ref "U3") (pin "PAD") (pinfunction "PAD_PAD") (pintype "power_in"))
      (node (ref "U4") (pin "3") (pinfunction "GND_3") (pintype "power_in"))
    )
    (net (code "65") (name "Net-(D2-A)") (class "Default")
      (node (ref "D2") (pin "2") (pinfunction "A_2") (pintype "passive"))
      (node (ref "R11") (pin "1") (pinfunction "1_1") (pintype "passive"))
    )
    (net (code "66") (name "Net-(D3-A)") (class "Default")
      (node (ref "D3") (pin "2") (pinfunction "A_2") (pintype "passive"))
      (node (ref "R13") (pin "1") (pinfunction "1_1") (pintype "passive"))
    )
    (net (code "67") (name "Net-(M1-+3.3VD_IN-Pad25)") (class "Default")
      (node (ref "M1") (pin "25") (pinfunction "+3.3VD_IN_25") (pintype "power_in"))
      (node (ref "M1") (pin "26") (pinfunction "+3.3VD_IN_26") (pintype "power_in"))
      (node (ref "R11") (pin "2") (pinfunction "2_2") (pintype "passive"))
      (node (ref "R12") (pin "2") (pinfunction "2_2") (pintype "passive"))
    )
    (net (code "68") (name "Net-(TP1-PP)") (class "Default")
      (node (ref "TP1") (pin "1") (pinfunction "PP_1") (pintype "passive"))
      (node (ref "U3") (pin "1") (pinfunction "RI_1") (pintype "input"))
    )
    (net (code "69") (name "Net-(TP3-PP)") (class "Default")
      (node (ref "TP3") (pin "1") (pinfunction "PP_1") (pintype "passive"))
      (node (ref "U3") (pin "11") (pinfunction "GPIO.3_11") (pintype "bidirectional"))
    )
    (net (code "70") (name "Net-(TP4-PP)") (class "Default")
      (node (ref "TP4") (pin "1") (pinfunction "PP_1") (pintype "passive"))
      (node (ref "U3") (pin "12") (pinfunction "GPIO.2_12") (pintype "bidirectional"))
    )
    (net (code "71") (name "Net-(TP5-PP)") (class "Default")
      (node (ref "TP5") (pin "1") (pinfunction "PP_1") (pintype "passive"))
      (node (ref "U3") (pin "13") (pinfunction "GPIO.1_13") (pintype "bidirectional"))
    )
    (net (code "72") (name "Net-(TP6-PP)") (class "Default")
      (node (ref "TP6") (pin "1") (pinfunction "PP_1") (pintype "passive"))
      (node (ref "U3") (pin "14") (pinfunction "GPIO.0_14") (pintype "bidirectional"))
    )
    (net (code "73") (name "Net-(TP9-PP)") (class "Default")
      (node (ref "TP9") (pin "1") (pinfunction "PP_1") (pintype "passive"))
      (node (ref "U3") (pin "22") (pinfunction "DSR_22") (pintype "input"))
    )
    (net (code "74") (name "Net-(TP10-PP)") (class "Default")
      (node (ref "TP10") (pin "1") (pinfunction "PP_1") (pintype "passive"))
      (node (ref "U3") (pin "23") (pinfunction "DTR_23") (pintype "output"))
    )
    (net (code "75") (name "Net-(TP11-PP)") (class "Default")
      (node (ref "TP11") (pin "1") (pinfunction "PP_1") (pintype "passive"))
      (node (ref "U3") (pin "24") (pinfunction "DCD_24") (pintype "input"))
    )
    (net (code "76") (name "Net-(U3-VDD)") (class "Default")
      (node (ref "C10") (pin "1") (pinfunction "1_1") (pintype "passive"))
      (node (ref "C9") (pin "1") (pinfunction "1_1") (pintype "passive"))
      (node (ref "U3") (pin "6") (pinfunction "VDD_6") (pintype "power_in"))
    )
    (net (code "77") (name "Net-(U3-VPP)") (class "Default")
      (node (ref "C19") (pin "1") (pinfunction "1_1") (pintype "passive"))
      (node (ref "U3") (pin "16") (pinfunction "VPP_16") (pintype "passive"))
    )
    (net (code "78") (name "PE") (class "Default")
      (node (ref "C2") (pin "1") (pinfunction "1_1") (pintype "passive"))
      (node (ref "S1") (pin "SH$1") (pinfunction "M0_SH$1") (pintype "passive"))
      (node (ref "S1") (pin "SH$2") (pinfunction "M1_SH$2") (pintype "passive"))
      (node (ref "S1") (pin "SH$3") (pinfunction "M2_SH$3") (pintype "passive"))
      (node (ref "S1") (pin "SH$4") (pinfunction "M3_SH$4") (pintype "passive"))
    )
    (net (code "79") (name "unconnected-(S1-Pad4)") (class "Default")
      (node (ref "S1") (pin "4") (pinfunction "4_4") (pintype "passive"))
    )
    (net (code "80") (name "unconnected-(U2-PG-Pad8)") (class "Default")
      (node (ref "U2") (pin "8") (pinfunction "PG_8") (pintype "open_collector"))
    )
    (net (code "81") (name "unconnected-(U3-NC-Pad10)") (class "Default")
      (node (ref "U3") (pin "10") (pinfunction "NC_10") (pintype "no_connect"))
    )
    (net (code "82") (name "unconnected-(U3-SUSPEND-Pad17)") (class "Default")
      (node (ref "U3") (pin "17") (pinfunction "SUSPEND_17") (pintype "output"))
    )
    (net (code "83") (name "unconnected-(U3-~{RST}-Pad9)") (class "Default")
      (node (ref "U3") (pin "9") (pinfunction "~{RST}_9") (pintype "bidirectional"))
    )
    (net (code "84") (name "unconnected-(U3-~{SUSPEND}-Pad15)") (class "Default")
      (node (ref "U3") (pin "15") (pinfunction "~{SUSPEND}_15") (pintype "output"))
    )
  )
)
